# v1.net
KiCad netlist of a schematic drawn in EAGLE
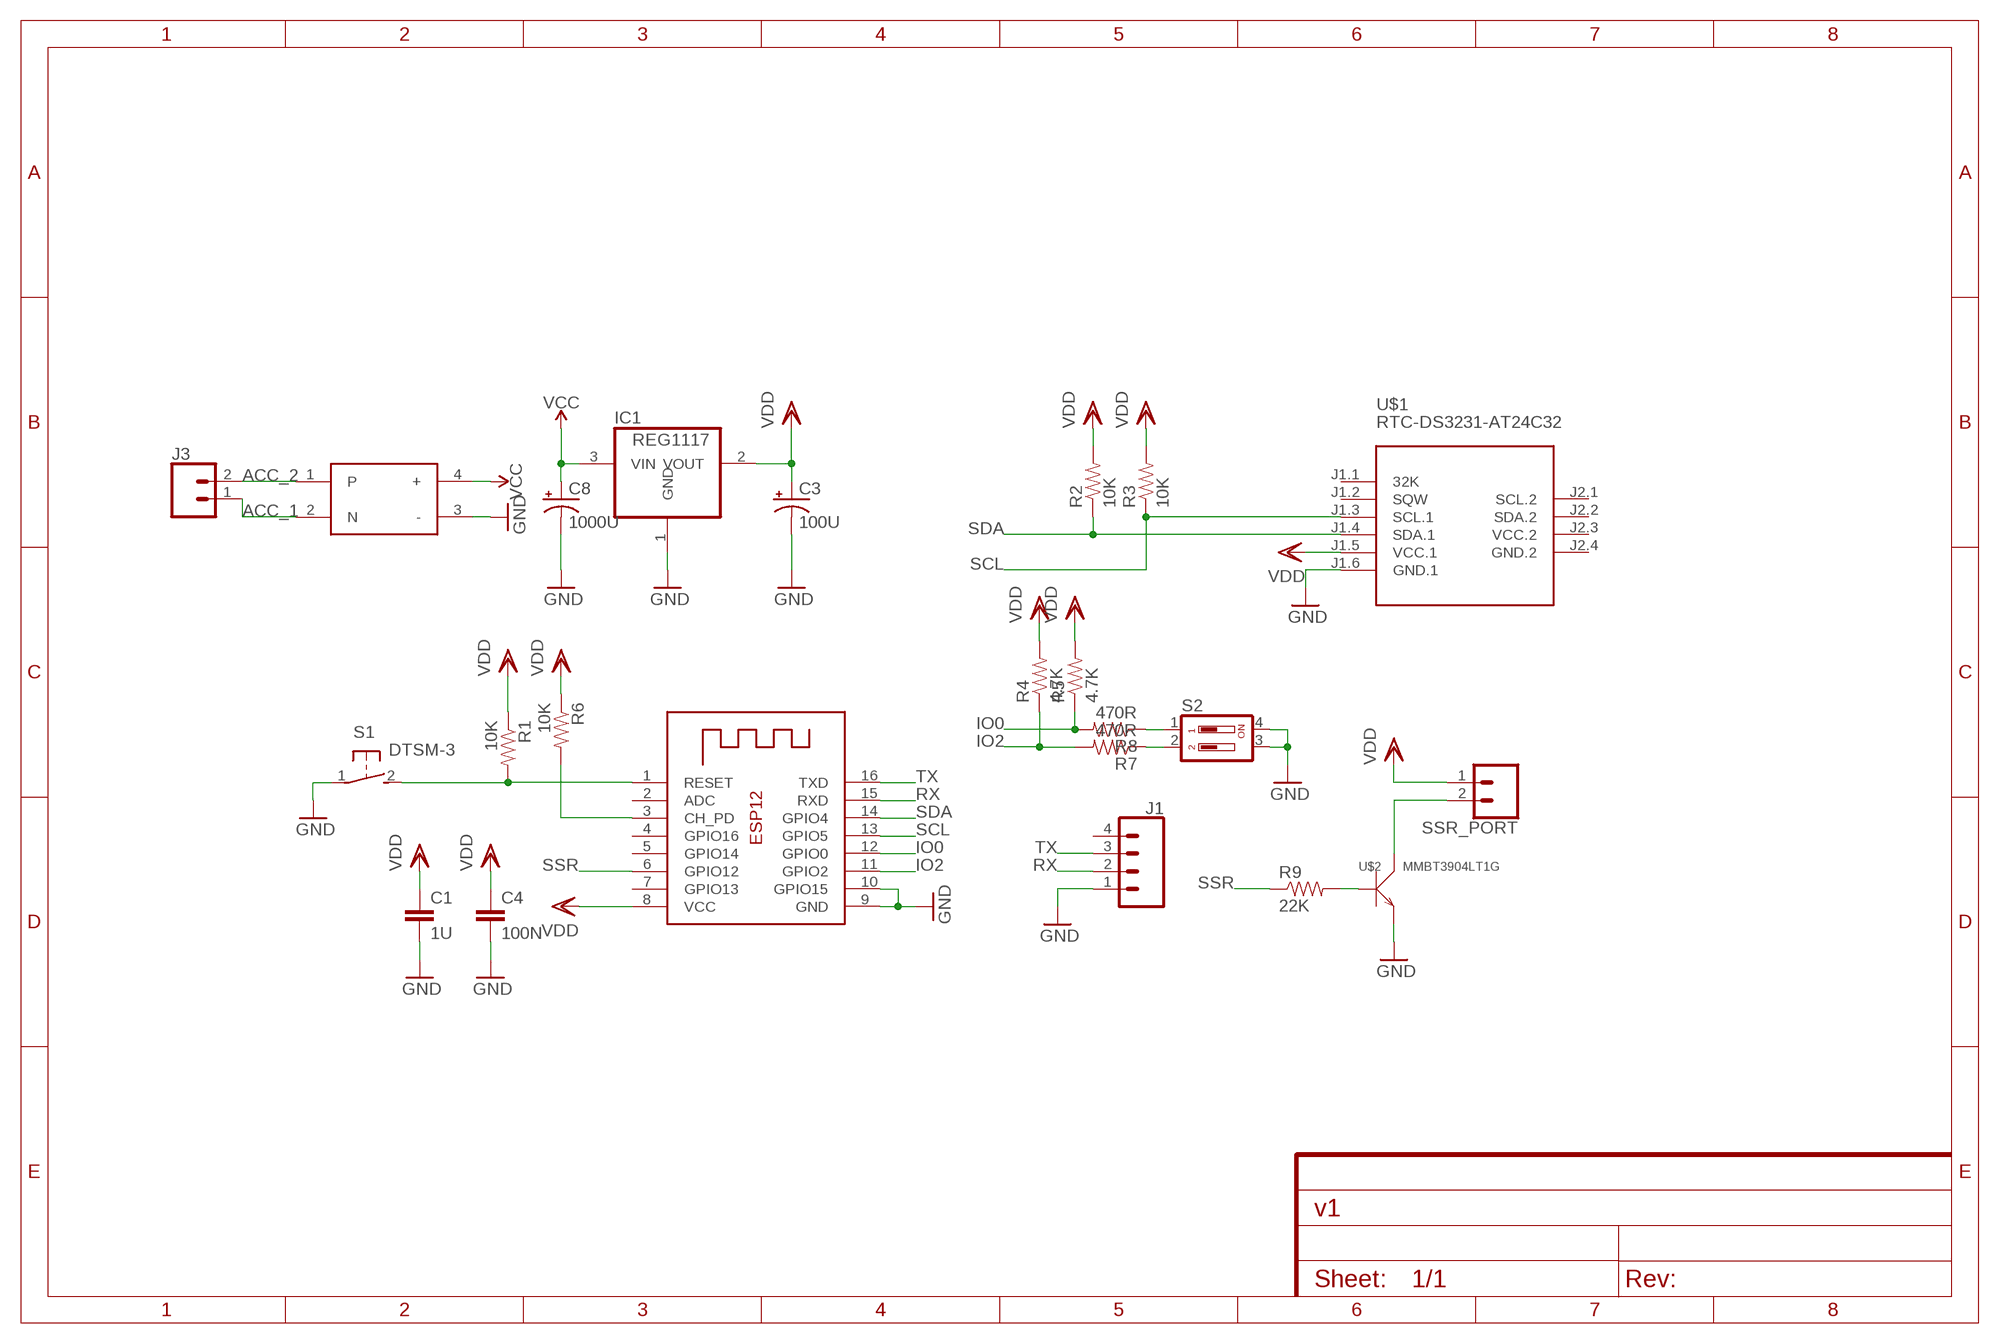
[diagram p0: schematic, sheet 1]

(export (version "E")
  (design (tool "Eeschema 10.0.6"))
  (components
    (comp (ref "C1")
      (value "1U")
      (footprint "eagle-import:1206")
      (libsource (lib "eagle-import") (part "CAP1206"))
    )
    (comp (ref "C3")
      (value "100U")
      (footprint "eagle-import:CPOL-RADIAL-100UF-25V")
      (libsource (lib "eagle-import") (part "CAP_POLPTH1"))
    )
    (comp (ref "C4")
      (value "100N")
      (footprint "eagle-import:1206")
      (libsource (lib "eagle-import") (part "CAP1206"))
    )
    (comp (ref "C8")
      (value "1000U")
      (footprint "eagle-import:CPOL-RADIAL-5MM-10MM")
      (libsource (lib "eagle-import") (part "1000UF-RADIAL-5MM-25V-20%"))
    )
    (comp (ref "IC1")
      (value "REG1117")
      (footprint "eagle-import:SOT223")
      (libsource (lib "eagle-import") (part "REG1117"))
    )
    (comp (ref "J1")
      (value "CONN_04")
      (footprint "eagle-import:1X04")
      (libsource (lib "eagle-import") (part "CONN_04"))
    )
    (comp (ref "J3")
      (value "CONN_023.5MM")
      (footprint "eagle-import:SCREWTERMINAL-3.5MM-2")
      (libsource (lib "eagle-import") (part "CONN_023.5MM"))
    )
    (comp (ref "R1")
      (value "10K")
      (footprint "eagle-import:1206")
      (libsource (lib "eagle-import") (part "RESISTOR1206"))
    )
    (comp (ref "R2")
      (value "10K")
      (footprint "eagle-import:1206")
      (libsource (lib "eagle-import") (part "RESISTOR1206"))
    )
    (comp (ref "R3")
      (value "10K")
      (footprint "eagle-import:1206")
      (libsource (lib "eagle-import") (part "RESISTOR1206"))
    )
    (comp (ref "R4")
      (value "4.7K")
      (footprint "eagle-import:1206")
      (libsource (lib "eagle-import") (part "RESISTOR1206"))
    )
    (comp (ref "R5")
      (value "4.7K")
      (footprint "eagle-import:1206")
      (libsource (lib "eagle-import") (part "RESISTOR1206"))
    )
    (comp (ref "R6")
      (value "10K")
      (footprint "eagle-import:1206")
      (libsource (lib "eagle-import") (part "RESISTOR1206"))
    )
    (comp (ref "R7")
      (value "470R")
      (footprint "eagle-import:1206")
      (libsource (lib "eagle-import") (part "RESISTOR1206"))
    )
    (comp (ref "R8")
      (value "470R")
      (footprint "eagle-import:1206")
      (libsource (lib "eagle-import") (part "RESISTOR1206"))
    )
    (comp (ref "R9")
      (value "22K")
      (footprint "eagle-import:1206")
      (libsource (lib "eagle-import") (part "RESISTOR1206"))
    )
    (comp (ref "S1")
      (value "DTSM-3")
      (footprint "eagle-import:DTSM-3")
      (libsource (lib "eagle-import") (part "DTSM-3"))
    )
    (comp (ref "S2")
      (value "DP02")
      (footprint "eagle-import:DP-02")
      (fields (field (name "MPN") "MCDP02"))
      (libsource (lib "eagle-import") (part "DP02"))
    )
    (comp (ref "SSR_PORT")
      (value "CONN_023.5MM")
      (footprint "eagle-import:SCREWTERMINAL-3.5MM-2")
      (libsource (lib "eagle-import") (part "CONN_023.5MM"))
    )
    (comp (ref "U$1")
      (value "RTC-DS3231-AT24C32")
      (footprint "eagle-import:RTC-DS3231-AT24C32")
      (libsource (lib "eagle-import") (part "RTC-DS3231-AT24C32"))
    )
    (comp (ref "U$2")
      (value "MMBT3904LT1G")
      (footprint "eagle-import:SOT-23")
      (libsource (lib "eagle-import") (part "SMD-TRANSISTORS-NPN-40V-200MA-MMBT3904LT1G(SOT-23)"))
    )
    (comp (ref "U$3")
      (value "AC_DC")
      (footprint "eagle-import:AC_DC")
      (libsource (lib "eagle-import") (part "AC_DC"))
    )
    (comp (ref "X1")
      (value "ESP-12")
      (footprint "eagle-import:ESP-12")
      (libsource (lib "eagle-import") (part "ESP-12"))
    )
  )
  (nets
    (net (code "1") (name "/ACC_1") (class "Default")
      (node (ref "J3") (pin "1") (pinfunction "1_1") (pintype "passive"))
      (node (ref "U$3") (pin "2") (pinfunction "N_2") (pintype "bidirectional"))
    )
    (net (code "2") (name "/ACC_2") (class "Default")
      (node (ref "J3") (pin "2") (pinfunction "2_2") (pintype "passive"))
      (node (ref "U$3") (pin "1") (pinfunction "P_1") (pintype "bidirectional"))
    )
    (net (code "3") (name "/GND.2") (class "Default")
      (node (ref "U$1") (pin "J2.4") (pinfunction "GND.2_J2.4") (pintype "power_in"))
    )
    (net (code "4") (name "/IO0") (class "Default")
      (node (ref "R5") (pin "1") (pinfunction "1_1") (pintype "passive"))
      (node (ref "R8") (pin "2") (pinfunction "2_2") (pintype "passive"))
      (node (ref "X1") (pin "12") (pinfunction "GPIO0_12") (pintype "bidirectional"))
    )
    (net (code "5") (name "/IO2") (class "Default")
      (node (ref "R4") (pin "1") (pinfunction "1_1") (pintype "passive"))
      (node (ref "R7") (pin "2") (pinfunction "2_2") (pintype "passive"))
      (node (ref "X1") (pin "11") (pinfunction "GPIO2_11") (pintype "bidirectional"))
    )
    (net (code "6") (name "/RX") (class "Default")
      (node (ref "J1") (pin "2") (pinfunction "2_2") (pintype "passive"))
      (node (ref "X1") (pin "15") (pinfunction "RXD_15") (pintype "input"))
    )
    (net (code "7") (name "/SCL") (class "Default")
      (node (ref "R3") (pin "1") (pinfunction "1_1") (pintype "passive"))
      (node (ref "U$1") (pin "J1.3") (pinfunction "SCL.1_J1.3") (pintype "bidirectional"))
      (node (ref "X1") (pin "13") (pinfunction "GPIO5_13") (pintype "bidirectional"))
    )
    (net (code "8") (name "/SDA") (class "Default")
      (node (ref "R2") (pin "1") (pinfunction "1_1") (pintype "passive"))
      (node (ref "U$1") (pin "J1.4") (pinfunction "SDA.1_J1.4") (pintype "bidirectional"))
      (node (ref "X1") (pin "14") (pinfunction "GPIO4_14") (pintype "bidirectional"))
    )
    (net (code "9") (name "/SSR") (class "Default")
      (node (ref "R9") (pin "1") (pinfunction "1_1") (pintype "passive"))
      (node (ref "X1") (pin "6") (pinfunction "GPIO12_6") (pintype "bidirectional"))
    )
    (net (code "10") (name "/TX") (class "Default")
      (node (ref "J1") (pin "3") (pinfunction "3_3") (pintype "passive"))
      (node (ref "X1") (pin "16") (pinfunction "TXD_16") (pintype "output"))
    )
    (net (code "11") (name "/VCC.2") (class "Default")
      (node (ref "U$1") (pin "J2.3") (pinfunction "VCC.2_J2.3") (pintype "power_in"))
    )
    (net (code "12") (name "GND") (class "Default")
      (node (ref "C1") (pin "2") (pinfunction "2_2") (pintype "passive"))
      (node (ref "C3") (pin "2") (pinfunction "-_2") (pintype "passive"))
      (node (ref "C4") (pin "2") (pinfunction "2_2") (pintype "passive"))
      (node (ref "C8") (pin "-") (pinfunction "-_-") (pintype "passive"))
      (node (ref "IC1") (pin "1") (pinfunction "GND_1") (pintype "power_in"))
      (node (ref "J1") (pin "1") (pinfunction "1_1") (pintype "passive"))
      (node (ref "S1") (pin "1") (pinfunction "1_1") (pintype "passive"))
      (node (ref "S2") (pin "3") (pinfunction "3_3") (pintype "passive"))
      (node (ref "S2") (pin "4") (pinfunction "4_4") (pintype "passive"))
      (node (ref "U$1") (pin "J1.6") (pinfunction "GND.1_J1.6") (pintype "power_in"))
      (node (ref "U$2") (pin "2") (pinfunction "E_2") (pintype "passive"))
      (node (ref "U$3") (pin "3") (pinfunction "-_3") (pintype "bidirectional"))
      (node (ref "X1") (pin "10") (pinfunction "GPIO15_10") (pintype "bidirectional"))
      (node (ref "X1") (pin "9") (pinfunction "GND_9") (pintype "power_in"))
    )
    (net (code "13") (name "Net-(R7-Pad1)") (class "Default")
      (node (ref "R7") (pin "1") (pinfunction "1_1") (pintype "passive"))
      (node (ref "S2") (pin "2") (pinfunction "2_2") (pintype "passive"))
    )
    (net (code "14") (name "Net-(R8-Pad1)") (class "Default")
      (node (ref "R8") (pin "1") (pinfunction "1_1") (pintype "passive"))
      (node (ref "S2") (pin "1") (pinfunction "1_1") (pintype "passive"))
    )
    (net (code "15") (name "Net-(U$2-B)") (class "Default")
      (node (ref "R9") (pin "2") (pinfunction "2_2") (pintype "passive"))
      (node (ref "U$2") (pin "1") (pinfunction "B_1") (pintype "passive"))
    )
    (net (code "16") (name "Net-(U$2-C)") (class "Default")
      (node (ref "SSR_PORT") (pin "2") (pinfunction "2_2") (pintype "passive"))
      (node (ref "U$2") (pin "3") (pinfunction "C_3") (pintype "passive"))
    )
    (net (code "17") (name "Net-(X1-CH_PD)") (class "Default")
      (node (ref "R6") (pin "2") (pinfunction "2_2") (pintype "passive"))
      (node (ref "X1") (pin "3") (pinfunction "CH_PD_3") (pintype "input"))
    )
    (net (code "18") (name "Net-(X1-RESET)") (class "Default")
      (node (ref "R1") (pin "2") (pinfunction "2_2") (pintype "passive"))
      (node (ref "S1") (pin "2") (pinfunction "2_2") (pintype "passive"))
      (node (ref "X1") (pin "1") (pinfunction "RESET_1") (pintype "input"))
    )
    (net (code "19") (name "VCC") (class "Default")
      (node (ref "C8") (pin "+") (pinfunction "+_+") (pintype "passive"))
      (node (ref "IC1") (pin "3") (pinfunction "VIN_3") (pintype "input"))
      (node (ref "U$3") (pin "4") (pinfunction "+_4") (pintype "bidirectional"))
    )
    (net (code "20") (name "VDD") (class "Default")
      (node (ref "C1") (pin "1") (pinfunction "1_1") (pintype "passive"))
      (node (ref "C3") (pin "1") (pinfunction "+_1") (pintype "passive"))
      (node (ref "C4") (pin "1") (pinfunction "1_1") (pintype "passive"))
      (node (ref "IC1") (pin "2") (pinfunction "VOUT_2") (pintype "output"))
      (node (ref "R1") (pin "1") (pinfunction "1_1") (pintype "passive"))
      (node (ref "R2") (pin "2") (pinfunction "2_2") (pintype "passive"))
      (node (ref "R3") (pin "2") (pinfunction "2_2") (pintype "passive"))
      (node (ref "R4") (pin "2") (pinfunction "2_2") (pintype "passive"))
      (node (ref "R5") (pin "2") (pinfunction "2_2") (pintype "passive"))
      (node (ref "R6") (pin "1") (pinfunction "1_1") (pintype "passive"))
      (node (ref "SSR_PORT") (pin "1") (pinfunction "1_1") (pintype "passive"))
      (node (ref "U$1") (pin "J1.5") (pinfunction "VCC.1_J1.5") (pintype "power_in"))
      (node (ref "X1") (pin "8") (pinfunction "VCC_8") (pintype "power_in"))
    )
    (net (code "21") (name "unconnected-(J1-Pad4)") (class "Default")
      (node (ref "J1") (pin "4") (pinfunction "4_4") (pintype "passive"))
    )
    (net (code "22") (name "unconnected-(U$1-32K-PadJ1.1)") (class "Default")
      (node (ref "U$1") (pin "J1.1") (pinfunction "32K_J1.1") (pintype "bidirectional"))
    )
    (net (code "23") (name "unconnected-(U$1-SCL.2-PadJ2.1)") (class "Default")
      (node (ref "U$1") (pin "J2.1") (pinfunction "SCL.2_J2.1") (pintype "bidirectional"))
    )
    (net (code "24") (name "unconnected-(U$1-SDA.2-PadJ2.2)") (class "Default")
      (node (ref "U$1") (pin "J2.2") (pinfunction "SDA.2_J2.2") (pintype "bidirectional"))
    )
    (net (code "25") (name "unconnected-(U$1-SQW-PadJ1.2)") (class "Default")
      (node (ref "U$1") (pin "J1.2") (pinfunction "SQW_J1.2") (pintype "bidirectional"))
    )
    (net (code "26") (name "unconnected-(X1-ADC-Pad2)") (class "Default")
      (node (ref "X1") (pin "2") (pinfunction "ADC_2") (pintype "passive"))
    )
    (net (code "27") (name "unconnected-(X1-GPIO13-Pad7)") (class "Default")
      (node (ref "X1") (pin "7") (pinfunction "GPIO13_7") (pintype "bidirectional"))
    )
    (net (code "28") (name "unconnected-(X1-GPIO14-Pad5)") (class "Default")
      (node (ref "X1") (pin "5") (pinfunction "GPIO14_5") (pintype "bidirectional"))
    )
    (net (code "29") (name "unconnected-(X1-GPIO16-Pad4)") (class "Default")
      (node (ref "X1") (pin "4") (pinfunction "GPIO16_4") (pintype "bidirectional"))
    )
  )
)
